# UIAPduino_Pro_Micro_CH32V006_V1dot0.net
KiCad netlist of a schematic drawn in EAGLE
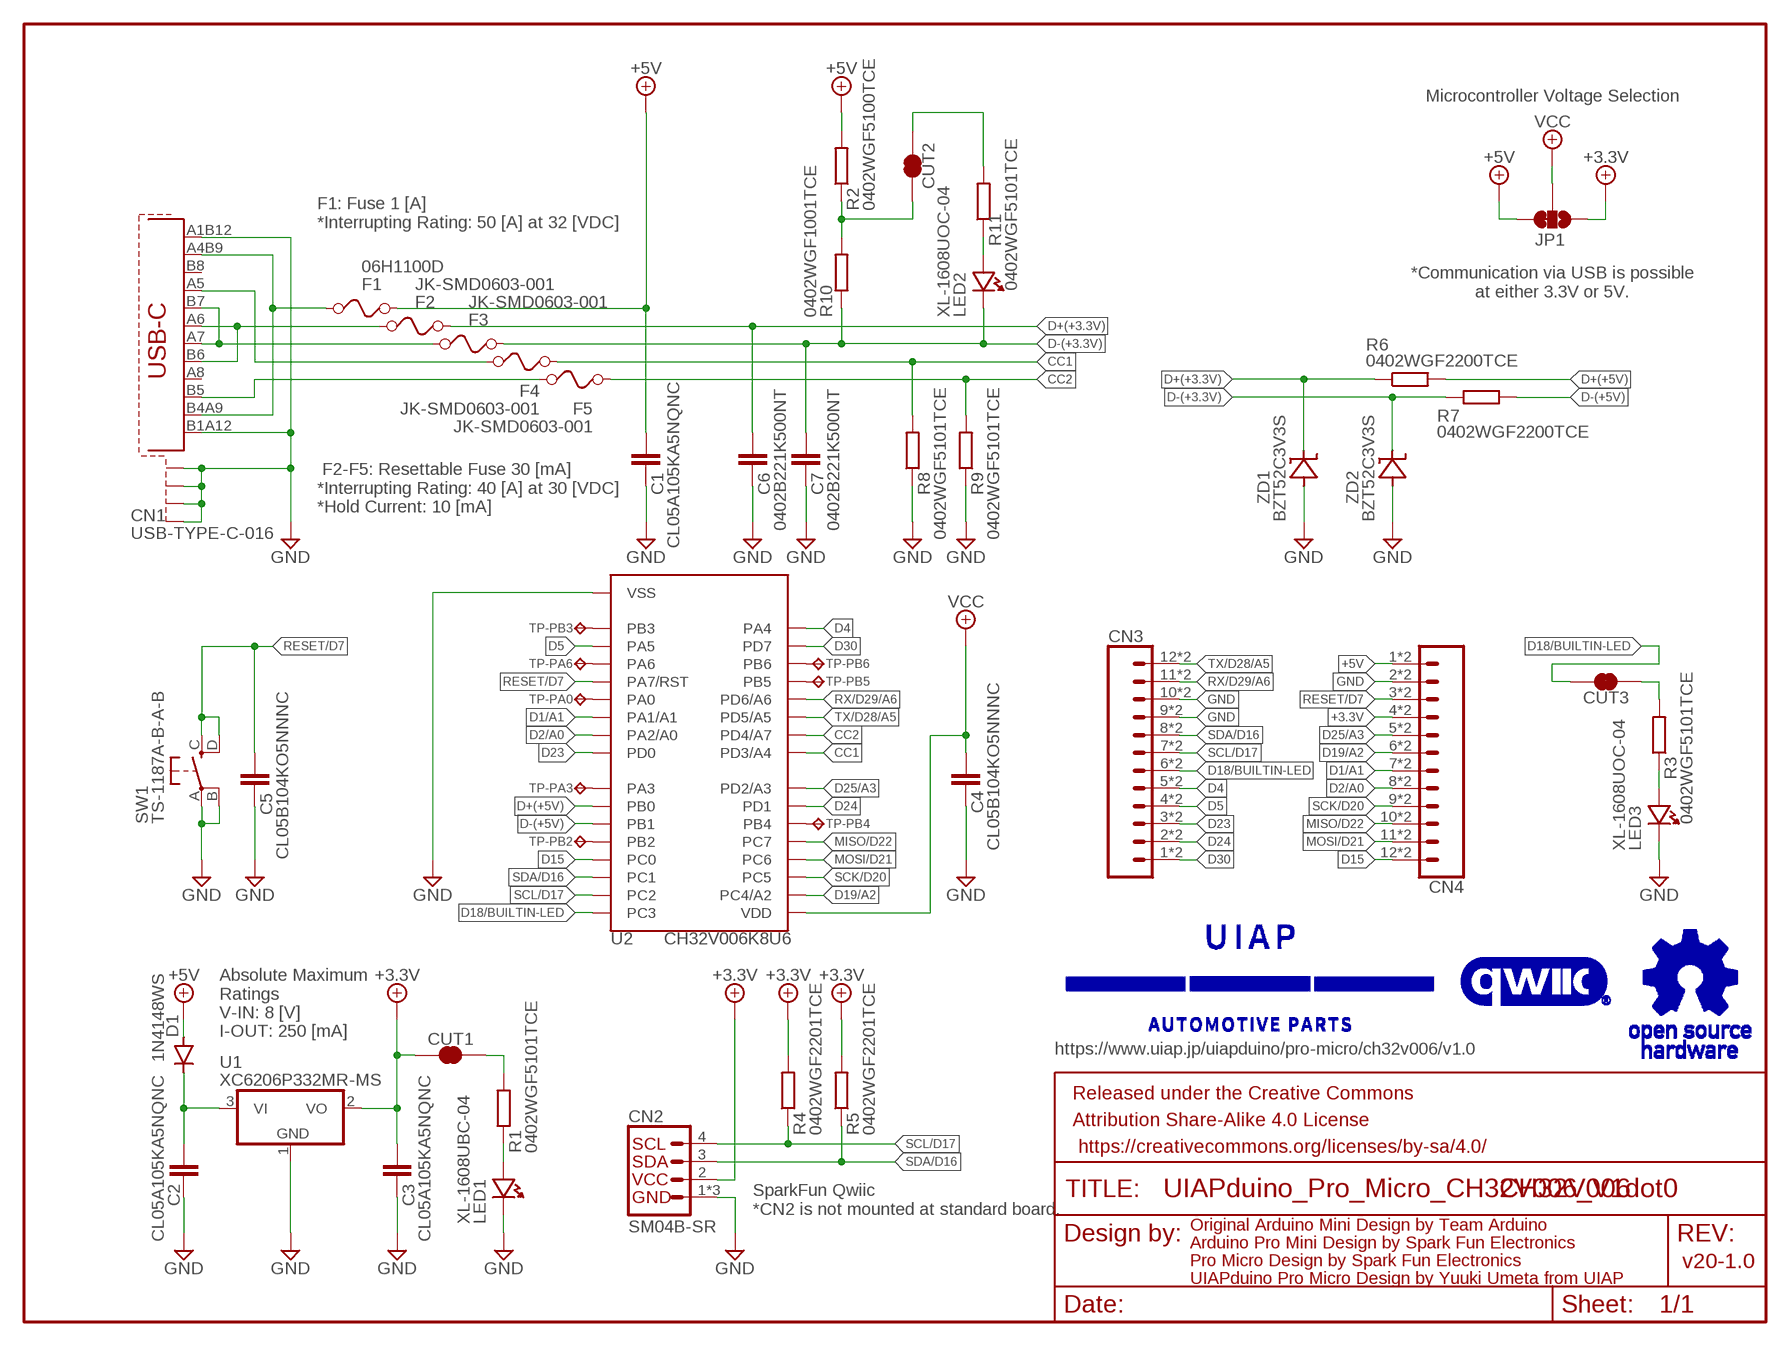
[diagram p0: schematic, sheet 1, part 1 of 2]
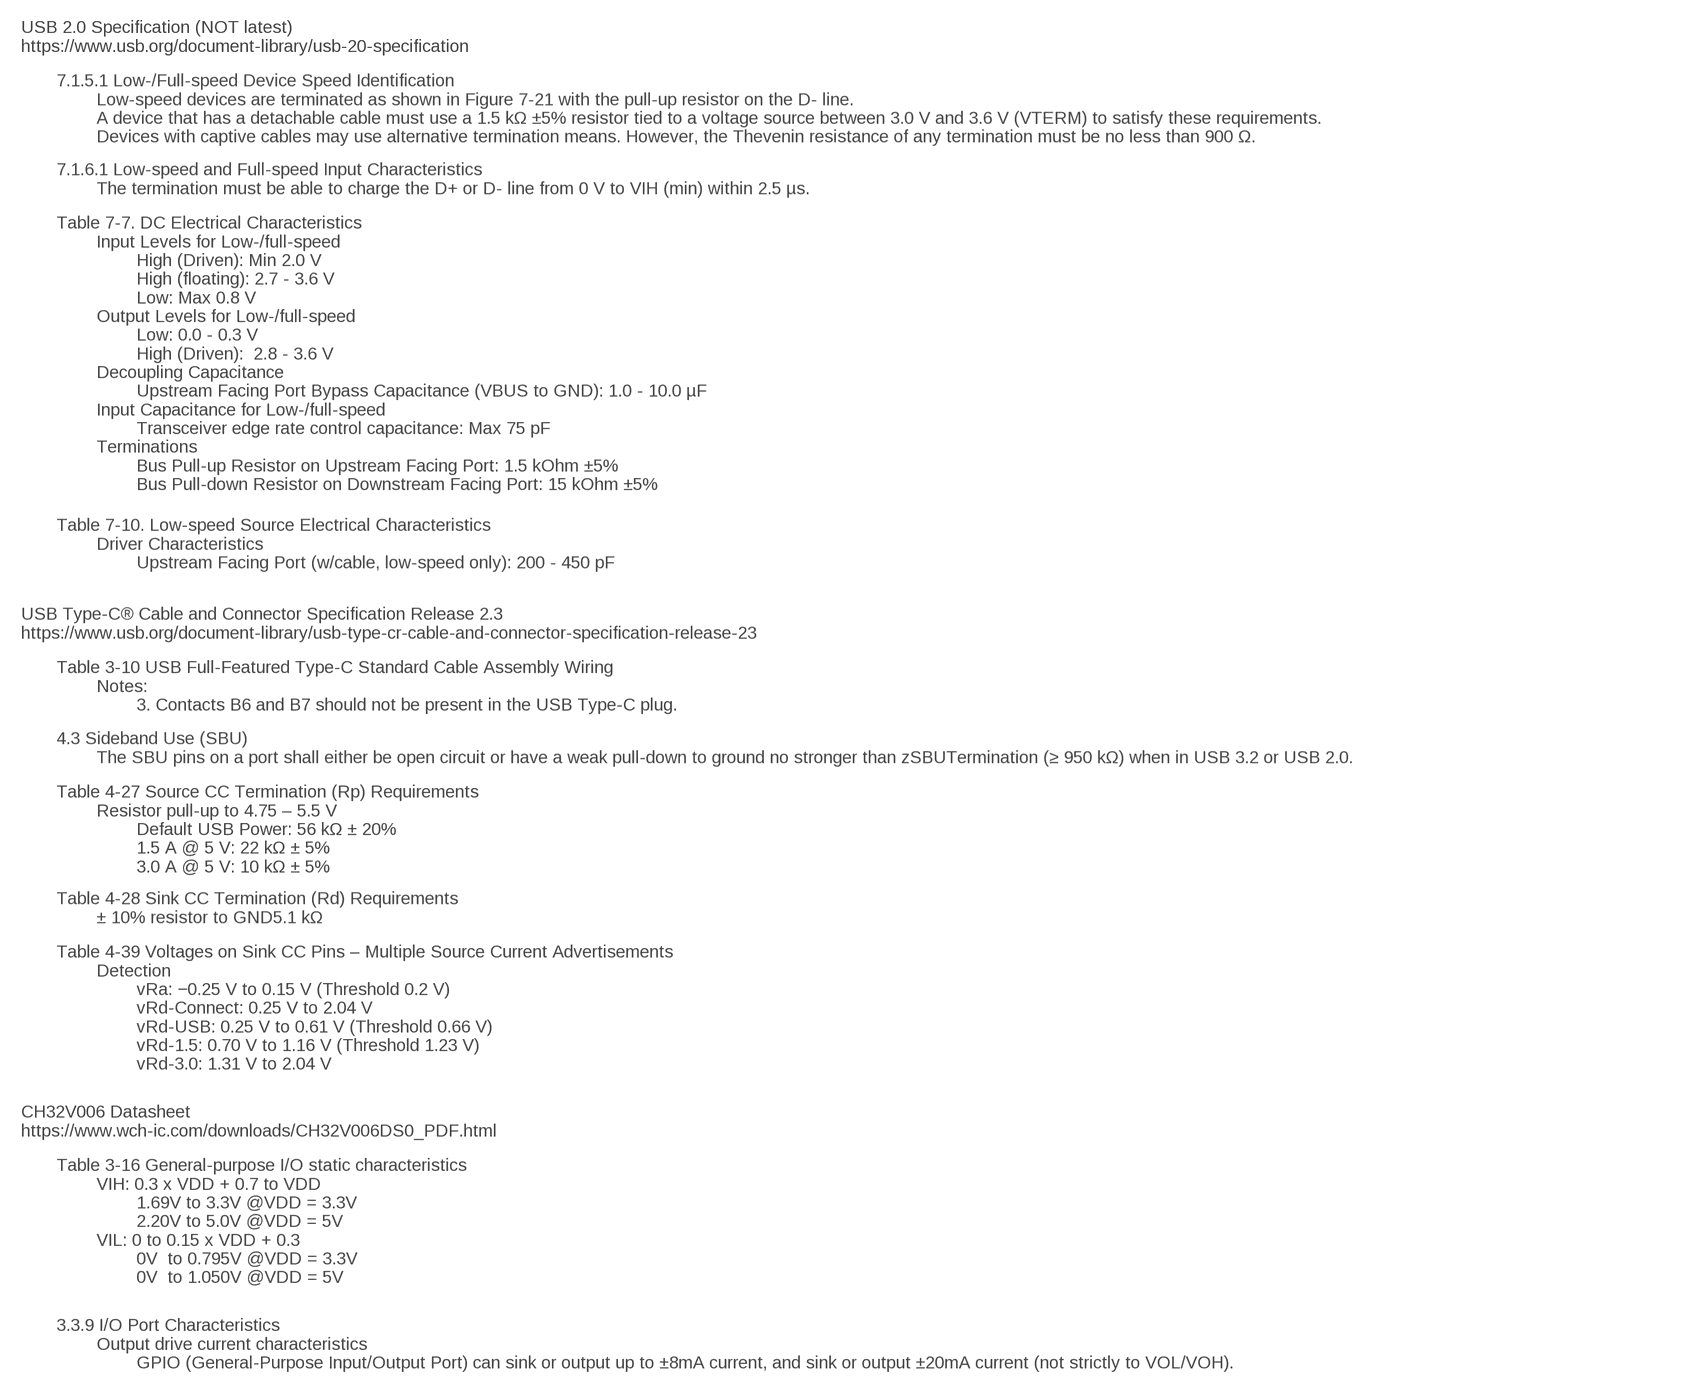
[diagram p1: schematic, sheet 1, part 2 of 2]

(export (version "E")
  (design (tool "Eeschema 10.0.6"))
  (components
    (comp (ref "C1")
      (value "CL05A105KA5NQNC")
      (footprint "eagle-import:1005")
      (libsource (lib "eagle-import") (part "C1005"))
    )
    (comp (ref "C2")
      (value "CL05A105KA5NQNC")
      (footprint "eagle-import:1005")
      (libsource (lib "eagle-import") (part "C1005"))
    )
    (comp (ref "C3")
      (value "CL05A105KA5NQNC")
      (footprint "eagle-import:1005")
      (libsource (lib "eagle-import") (part "C1005"))
    )
    (comp (ref "C4")
      (value "CL05B104KO5NNNC")
      (footprint "eagle-import:1005")
      (libsource (lib "eagle-import") (part "C1005"))
    )
    (comp (ref "C5")
      (value "CL05B104KO5NNNC")
      (footprint "eagle-import:1005")
      (libsource (lib "eagle-import") (part "C1005"))
    )
    (comp (ref "C6")
      (value "0402B221K500NT")
      (footprint "eagle-import:1005")
      (libsource (lib "eagle-import") (part "C1005"))
    )
    (comp (ref "C7")
      (value "0402B221K500NT")
      (footprint "eagle-import:1005")
      (libsource (lib "eagle-import") (part "C1005"))
    )
    (comp (ref "CN1")
      (value "USB-TYPE-C-016")
      (footprint "eagle-import:USB-TYPE-C-016")
      (libsource (lib "eagle-import") (part "USB-TYPE-C-016"))
    )
    (comp (ref "CN2")
      (value "SM04B-SR")
      (footprint "eagle-import:JST04_1MM_RA")
      (libsource (lib "eagle-import") (part "QWIIC_CONNECTORJS-1MM-GND"))
    )
    (comp (ref "CN3")
      (value "CONN_12CASTLE_0.9MM")
      (footprint "eagle-import:1X12_CASTELLATED_0.9MM")
      (libsource (lib "eagle-import") (part "CONN_12CASTLE_0.9MM"))
    )
    (comp (ref "CN4")
      (value "CONN_12CASTLE_0.9MM")
      (footprint "eagle-import:1X12_CASTELLATED_0.9MM")
      (libsource (lib "eagle-import") (part "CONN_12CASTLE_0.9MM"))
    )
    (comp (ref "CUT1")
      (value "SMT-JP-2-NC")
      (footprint "eagle-import:SMT-JUMPER_2_NC_SILK_ROUND")
      (libsource (lib "eagle-import") (part "SMT-JP-2-NC"))
    )
    (comp (ref "CUT2")
      (value "SMT-JP-2-NC")
      (footprint "eagle-import:SMT-JUMPER_2_NC_SILK_ROUND")
      (libsource (lib "eagle-import") (part "SMT-JP-2-NC"))
    )
    (comp (ref "CUT3")
      (value "SMT-JP-2-NC")
      (footprint "eagle-import:SMT-JUMPER_2_NC_SILK_ROUND")
      (libsource (lib "eagle-import") (part "SMT-JP-2-NC"))
    )
    (comp (ref "D1")
      (value "1N4148WS")
      (footprint "eagle-import:SOD323-R")
      (libsource (lib "eagle-import") (part "DIODE-SOD323-R"))
    )
    (comp (ref "F1")
      (value "06H1100D")
      (footprint "eagle-import:1608")
      (libsource (lib "eagle-import") (part "06H1100D"))
    )
    (comp (ref "F2")
      (value "JK-SMD0603-001")
      (footprint "eagle-import:1608")
      (libsource (lib "eagle-import") (part "06H1100D"))
    )
    (comp (ref "F3")
      (value "JK-SMD0603-001")
      (footprint "eagle-import:1608")
      (libsource (lib "eagle-import") (part "06H1100D"))
    )
    (comp (ref "F4")
      (value "JK-SMD0603-001")
      (footprint "eagle-import:1608")
      (libsource (lib "eagle-import") (part "06H1100D"))
    )
    (comp (ref "F5")
      (value "JK-SMD0603-001")
      (footprint "eagle-import:1608")
      (libsource (lib "eagle-import") (part "06H1100D"))
    )
    (comp (ref "FRAME1")
      (value "FRAME-LETTER")
      (footprint "eagle-import:CREATIVE_COMMONS")
      (libsource (lib "eagle-import") (part "FRAME-LETTER"))
    )
    (comp (ref "JP1")
      (value "SMT-JP-3-NO-NC")
      (footprint "eagle-import:SMT-JUMPER_3_1-NC_TRACE_SILK")
      (libsource (lib "eagle-import") (part "SMT-JP-3-NO-NC"))
    )
    (comp (ref "LED1")
      (value "XL-1608UBC-04")
      (footprint "eagle-import:1608-LED")
      (libsource (lib "eagle-import") (part "XL-1608UBC-04"))
    )
    (comp (ref "LED2")
      (value "XL-1608UOC-04")
      (footprint "eagle-import:1608-LED")
      (libsource (lib "eagle-import") (part "XL-1608UOC-04"))
    )
    (comp (ref "LED3")
      (value "XL-1608UOC-04")
      (footprint "eagle-import:1608-LED")
      (libsource (lib "eagle-import") (part "XL-1608UOC-04"))
    )
    (comp (ref "R1")
      (value "0402WGF5101TCE")
      (footprint "eagle-import:1005")
      (libsource (lib "eagle-import") (part "R1005"))
    )
    (comp (ref "R2")
      (value "0402WGF5100TCE")
      (footprint "eagle-import:1005")
      (libsource (lib "eagle-import") (part "R1005"))
    )
    (comp (ref "R3")
      (value "0402WGF5101TCE")
      (footprint "eagle-import:1005")
      (libsource (lib "eagle-import") (part "R1005"))
    )
    (comp (ref "R4")
      (value "0402WGF2201TCE")
      (footprint "eagle-import:1005")
      (libsource (lib "eagle-import") (part "R1005"))
    )
    (comp (ref "R5")
      (value "0402WGF2201TCE")
      (footprint "eagle-import:1005")
      (libsource (lib "eagle-import") (part "R1005"))
    )
    (comp (ref "R6")
      (value "0402WGF2200TCE")
      (footprint "eagle-import:1005")
      (libsource (lib "eagle-import") (part "R1005"))
    )
    (comp (ref "R7")
      (value "0402WGF2200TCE")
      (footprint "eagle-import:1005")
      (libsource (lib "eagle-import") (part "R1005"))
    )
    (comp (ref "R8")
      (value "0402WGF5101TCE")
      (footprint "eagle-import:1005")
      (libsource (lib "eagle-import") (part "R1005"))
    )
    (comp (ref "R9")
      (value "0402WGF5101TCE")
      (footprint "eagle-import:1005")
      (libsource (lib "eagle-import") (part "R1005"))
    )
    (comp (ref "R10")
      (value "0402WGF1001TCE")
      (footprint "eagle-import:1005")
      (libsource (lib "eagle-import") (part "R1005"))
    )
    (comp (ref "R11")
      (value "0402WGF5101TCE")
      (footprint "eagle-import:1005")
      (libsource (lib "eagle-import") (part "R1005"))
    )
    (comp (ref "SW1")
      (value "TS-1187A-B-A-B")
      (footprint "eagle-import:TS-1187A-B-A-B")
      (libsource (lib "eagle-import") (part "TS-1187A-B-A-B"))
    )
    (comp (ref "TP-PA0")
      (value "TPTP06R")
      (footprint "eagle-import:TP06R")
      (libsource (lib "eagle-import") (part "TPTP06R"))
    )
    (comp (ref "TP-PA3")
      (value "TPTP06R")
      (footprint "eagle-import:TP06R")
      (libsource (lib "eagle-import") (part "TPTP06R"))
    )
    (comp (ref "TP-PA6")
      (value "TPTP06R")
      (footprint "eagle-import:TP06R")
      (libsource (lib "eagle-import") (part "TPTP06R"))
    )
    (comp (ref "TP-PB2")
      (value "TPTP06R")
      (footprint "eagle-import:TP06R")
      (libsource (lib "eagle-import") (part "TPTP06R"))
    )
    (comp (ref "TP-PB3")
      (value "TPTP06R")
      (footprint "eagle-import:TP06R")
      (libsource (lib "eagle-import") (part "TPTP06R"))
    )
    (comp (ref "TP-PB4")
      (value "TPTP06R")
      (footprint "eagle-import:TP06R")
      (libsource (lib "eagle-import") (part "TPTP06R"))
    )
    (comp (ref "TP-PB5")
      (value "TPTP06R")
      (footprint "eagle-import:TP06R")
      (libsource (lib "eagle-import") (part "TPTP06R"))
    )
    (comp (ref "TP-PB6")
      (value "TPTP06R")
      (footprint "eagle-import:TP06R")
      (libsource (lib "eagle-import") (part "TPTP06R"))
    )
    (comp (ref "U1")
      (value "XC6206P332MR-MS")
      (footprint "eagle-import:SOT-23F_TOS")
      (libsource (lib "eagle-import") (part "XC6206P332MR-MS"))
    )
    (comp (ref "U2")
      (value "CH32V006K8U6")
      (footprint "eagle-import:QFN40P400X400X100-33T270")
      (libsource (lib "eagle-import") (part "CH32V006K8U6"))
    )
    (comp (ref "ZD1")
      (value "BZT52C3V3S")
      (footprint "eagle-import:SOD323-R")
      (libsource (lib "eagle-import") (part "BZT52C3V3S"))
    )
    (comp (ref "ZD2")
      (value "BZT52C3V3S")
      (footprint "eagle-import:SOD323-R")
      (libsource (lib "eagle-import") (part "BZT52C3V3S"))
    )
  )
  (nets
    (net (code "1") (name "+3.3V") (class "Default")
      (node (ref "C3") (pin "1") (pinfunction "1_1") (pintype "passive"))
      (node (ref "CN2") (pin "2") (pinfunction "2_2") (pintype "power_in"))
      (node (ref "CN4") (pin "4") (pinfunction "4_4") (pintype "passive"))
      (node (ref "CN4") (pin "4B") (pinfunction "4_4B") (pintype "passive"))
      (node (ref "CUT1") (pin "2") (pinfunction "2_2") (pintype "passive"))
      (node (ref "JP1") (pin "1") (pinfunction "1_1") (pintype "passive"))
      (node (ref "R4") (pin "2") (pinfunction "2_2") (pintype "passive"))
      (node (ref "R5") (pin "2") (pinfunction "2_2") (pintype "passive"))
      (node (ref "U1") (pin "2") (pinfunction "VO_2") (pintype "passive"))
    )
    (net (code "2") (name "+5V") (class "Default")
      (node (ref "C1") (pin "1") (pinfunction "1_1") (pintype "passive"))
      (node (ref "CN4") (pin "1") (pinfunction "1_1") (pintype "passive"))
      (node (ref "CN4") (pin "1B") (pinfunction "1_1B") (pintype "passive"))
      (node (ref "D1") (pin "A") (pinfunction "A_A") (pintype "passive"))
      (node (ref "F1") (pin "2") (pinfunction "2_2") (pintype "passive"))
      (node (ref "JP1") (pin "3") (pinfunction "3_3") (pintype "passive"))
      (node (ref "R2") (pin "2") (pinfunction "2_2") (pintype "passive"))
    )
    (net (code "3") (name "CC1") (class "Default")
      (node (ref "F4") (pin "2") (pinfunction "2_2") (pintype "passive"))
      (node (ref "R8") (pin "2") (pinfunction "2_2") (pintype "passive"))
      (node (ref "U2") (pin "25") (pinfunction "PD3/A4_25") (pintype "bidirectional"))
    )
    (net (code "4") (name "CC2") (class "Default")
      (node (ref "F5") (pin "2") (pinfunction "2_2") (pintype "passive"))
      (node (ref "R9") (pin "2") (pinfunction "2_2") (pintype "passive"))
      (node (ref "U2") (pin "26") (pinfunction "PD4/A7_26") (pintype "bidirectional"))
    )
    (net (code "5") (name "D+(+3.3V)") (class "Default")
      (node (ref "C6") (pin "1") (pinfunction "1_1") (pintype "passive"))
      (node (ref "F2") (pin "2") (pinfunction "2_2") (pintype "passive"))
      (node (ref "R6") (pin "1") (pinfunction "1_1") (pintype "passive"))
      (node (ref "ZD1") (pin "C") (pinfunction "C_C") (pintype "passive"))
    )
    (net (code "6") (name "D+(+5V)") (class "Default")
      (node (ref "R6") (pin "2") (pinfunction "2_2") (pintype "passive"))
      (node (ref "U2") (pin "10") (pinfunction "PB0_10") (pintype "bidirectional"))
    )
    (net (code "7") (name "D-(+3.3V)") (class "Default")
      (node (ref "C7") (pin "1") (pinfunction "1_1") (pintype "passive"))
      (node (ref "F3") (pin "2") (pinfunction "2_2") (pintype "passive"))
      (node (ref "LED2") (pin "2") (pinfunction "C_2") (pintype "passive"))
      (node (ref "R10") (pin "1") (pinfunction "1_1") (pintype "passive"))
      (node (ref "R7") (pin "1") (pinfunction "1_1") (pintype "passive"))
      (node (ref "ZD2") (pin "C") (pinfunction "C_C") (pintype "passive"))
    )
    (net (code "8") (name "D-(+5V)") (class "Default")
      (node (ref "R7") (pin "2") (pinfunction "2_2") (pintype "passive"))
      (node (ref "U2") (pin "11") (pinfunction "PB1_11") (pintype "bidirectional"))
    )
    (net (code "9") (name "D1{slash}A1") (class "Default")
      (node (ref "CN4") (pin "7") (pinfunction "7_7") (pintype "passive"))
      (node (ref "CN4") (pin "7B") (pinfunction "7_7B") (pintype "passive"))
      (node (ref "U2") (pin "6") (pinfunction "PA1/A1_6") (pintype "bidirectional"))
    )
    (net (code "10") (name "D2{slash}A0") (class "Default")
      (node (ref "CN4") (pin "8") (pinfunction "8_8") (pintype "passive"))
      (node (ref "CN4") (pin "8B") (pinfunction "8_8B") (pintype "passive"))
      (node (ref "U2") (pin "7") (pinfunction "PA2/A0_7") (pintype "bidirectional"))
    )
    (net (code "11") (name "D4") (class "Default")
      (node (ref "CN3") (pin "5") (pinfunction "5_5") (pintype "passive"))
      (node (ref "CN3") (pin "5B") (pinfunction "5_5B") (pintype "passive"))
      (node (ref "U2") (pin "32") (pinfunction "PA4_32") (pintype "bidirectional"))
    )
    (net (code "12") (name "D5") (class "Default")
      (node (ref "CN3") (pin "4") (pinfunction "4_4") (pintype "passive"))
      (node (ref "CN3") (pin "4B") (pinfunction "4_4B") (pintype "passive"))
      (node (ref "U2") (pin "2") (pinfunction "PA5_2") (pintype "bidirectional"))
    )
    (net (code "13") (name "D15") (class "Default")
      (node (ref "CN4") (pin "12") (pinfunction "12_12") (pintype "passive"))
      (node (ref "CN4") (pin "12B") (pinfunction "12_12B") (pintype "passive"))
      (node (ref "U2") (pin "13") (pinfunction "PC0_13") (pintype "bidirectional"))
    )
    (net (code "14") (name "D18{slash}BUILTIN-LED") (class "Default")
      (node (ref "CN3") (pin "6") (pinfunction "6_6") (pintype "passive"))
      (node (ref "CN3") (pin "6B") (pinfunction "6_6B") (pintype "passive"))
      (node (ref "CUT3") (pin "1") (pinfunction "1_1") (pintype "passive"))
      (node (ref "U2") (pin "16") (pinfunction "PC3_16") (pintype "bidirectional"))
    )
    (net (code "15") (name "D19{slash}A2") (class "Default")
      (node (ref "CN4") (pin "6") (pinfunction "6_6") (pintype "passive"))
      (node (ref "CN4") (pin "6B") (pinfunction "6_6B") (pintype "passive"))
      (node (ref "U2") (pin "18") (pinfunction "PC4/A2_18") (pintype "bidirectional"))
    )
    (net (code "16") (name "D23") (class "Default")
      (node (ref "CN3") (pin "3") (pinfunction "3_3") (pintype "passive"))
      (node (ref "CN3") (pin "3B") (pinfunction "3_3B") (pintype "passive"))
      (node (ref "U2") (pin "8") (pinfunction "PD0_8") (pintype "bidirectional"))
    )
    (net (code "17") (name "D24") (class "Default")
      (node (ref "CN3") (pin "2") (pinfunction "2_2") (pintype "passive"))
      (node (ref "CN3") (pin "2B") (pinfunction "2_2B") (pintype "passive"))
      (node (ref "U2") (pin "23") (pinfunction "PD1_23") (pintype "bidirectional"))
    )
    (net (code "18") (name "D25{slash}A3") (class "Default")
      (node (ref "CN4") (pin "5") (pinfunction "5_5") (pintype "passive"))
      (node (ref "CN4") (pin "5B") (pinfunction "5_5B") (pintype "passive"))
      (node (ref "U2") (pin "24") (pinfunction "PD2/A3_24") (pintype "bidirectional"))
    )
    (net (code "19") (name "D30") (class "Default")
      (node (ref "CN3") (pin "1") (pinfunction "1_1") (pintype "passive"))
      (node (ref "CN3") (pin "1B") (pinfunction "1_1B") (pintype "passive"))
      (node (ref "U2") (pin "31") (pinfunction "PD7_31") (pintype "bidirectional"))
    )
    (net (code "20") (name "GND") (class "Default")
      (node (ref "C1") (pin "2") (pinfunction "2_2") (pintype "passive"))
      (node (ref "C2") (pin "2") (pinfunction "2_2") (pintype "passive"))
      (node (ref "C3") (pin "2") (pinfunction "2_2") (pintype "passive"))
      (node (ref "C4") (pin "2") (pinfunction "2_2") (pintype "passive"))
      (node (ref "C5") (pin "2") (pinfunction "2_2") (pintype "passive"))
      (node (ref "C6") (pin "2") (pinfunction "2_2") (pintype "passive"))
      (node (ref "C7") (pin "2") (pinfunction "2_2") (pintype "passive"))
      (node (ref "CN1") (pin "A1B12") (pinfunction "GND_A1B12") (pintype "power_in"))
      (node (ref "CN1") (pin "B1A12") (pinfunction "GND_B1A12") (pintype "power_in"))
      (node (ref "CN1") (pin "S1") (pinfunction "S1_S1") (pintype "passive"))
      (node (ref "CN1") (pin "S1B") (pinfunction "S1_S1B") (pintype "passive"))
      (node (ref "CN1") (pin "S2") (pinfunction "S2_S2") (pintype "passive"))
      (node (ref "CN1") (pin "S2B") (pinfunction "S2_S2B") (pintype "passive"))
      (node (ref "CN1") (pin "S3") (pinfunction "S3_S3") (pintype "passive"))
      (node (ref "CN1") (pin "S3B") (pinfunction "S3_S3B") (pintype "passive"))
      (node (ref "CN1") (pin "S4") (pinfunction "S4_S4") (pintype "passive"))
      (node (ref "CN1") (pin "S4B") (pinfunction "S4_S4B") (pintype "passive"))
      (node (ref "CN2") (pin "1") (pinfunction "1_1") (pintype "power_in"))
      (node (ref "CN2") (pin "NC1") (pinfunction "1_NC1") (pintype "power_in"))
      (node (ref "CN2") (pin "NC2") (pinfunction "1_NC2") (pintype "power_in"))
      (node (ref "CN3") (pin "10") (pinfunction "10_10") (pintype "passive"))
      (node (ref "CN3") (pin "10B") (pinfunction "10_10B") (pintype "passive"))
      (node (ref "CN3") (pin "9") (pinfunction "9_9") (pintype "passive"))
      (node (ref "CN3") (pin "9B") (pinfunction "9_9B") (pintype "passive"))
      (node (ref "CN4") (pin "2") (pinfunction "2_2") (pintype "passive"))
      (node (ref "CN4") (pin "2B") (pinfunction "2_2B") (pintype "passive"))
      (node (ref "LED1") (pin "2") (pinfunction "C_2") (pintype "passive"))
      (node (ref "LED3") (pin "2") (pinfunction "C_2") (pintype "passive"))
      (node (ref "R8") (pin "1") (pinfunction "1_1") (pintype "passive"))
      (node (ref "R9") (pin "1") (pinfunction "1_1") (pintype "passive"))
      (node (ref "SW1") (pin "A") (pinfunction "P_A") (pintype "passive"))
      (node (ref "SW1") (pin "B") (pinfunction "P1_B") (pintype "passive"))
      (node (ref "U1") (pin "1") (pinfunction "GND_1") (pintype "passive"))
      (node (ref "U2") (pin "0") (pinfunction "VSS_0") (pintype "power_in"))
      (node (ref "U2") (pin "P-VIA$1") (pinfunction "VSS_P-VIA$1") (pintype "power_in"))
      (node (ref "U2") (pin "P-VIA$2") (pinfunction "VSS_P-VIA$2") (pintype "power_in"))
      (node (ref "U2") (pin "P-VIA$3") (pinfunction "VSS_P-VIA$3") (pintype "power_in"))
      (node (ref "U2") (pin "P-VIA$4") (pinfunction "VSS_P-VIA$4") (pintype "power_in"))
      (node (ref "U2") (pin "P-VIA$5") (pinfunction "VSS_P-VIA$5") (pintype "power_in"))
      (node (ref "U2") (pin "P-VIA$6") (pinfunction "VSS_P-VIA$6") (pintype "power_in"))
      (node (ref "U2") (pin "P-VIA$7") (pinfunction "VSS_P-VIA$7") (pintype "power_in"))
      (node (ref "U2") (pin "P-VIA$8") (pinfunction "VSS_P-VIA$8") (pintype "power_in"))
      (node (ref "U2") (pin "P-VIA$9") (pinfunction "VSS_P-VIA$9") (pintype "power_in"))
      (node (ref "ZD1") (pin "A") (pinfunction "A_A") (pintype "passive"))
      (node (ref "ZD2") (pin "A") (pinfunction "A_A") (pintype "passive"))
    )
    (net (code "21") (name "MISO{slash}D22") (class "Default")
      (node (ref "CN4") (pin "10") (pinfunction "10_10") (pintype "passive"))
      (node (ref "CN4") (pin "10B") (pinfunction "10_10B") (pintype "passive"))
      (node (ref "U2") (pin "21") (pinfunction "PC7_21") (pintype "bidirectional"))
    )
    (net (code "22") (name "MOSI{slash}D21") (class "Default")
      (node (ref "CN4") (pin "11") (pinfunction "11_11") (pintype "passive"))
      (node (ref "CN4") (pin "11B") (pinfunction "11_11B") (pintype "passive"))
      (node (ref "U2") (pin "20") (pinfunction "PC6_20") (pintype "bidirectional"))
    )
    (net (code "23") (name "Net-(CN1-CC1)") (class "Default")
      (node (ref "CN1") (pin "A5") (pinfunction "CC1_A5") (pintype "passive"))
      (node (ref "F4") (pin "1") (pinfunction "1_1") (pintype "passive"))
    )
    (net (code "24") (name "Net-(CN1-CC2)") (class "Default")
      (node (ref "CN1") (pin "B5") (pinfunction "CC2_B5") (pintype "passive"))
      (node (ref "F5") (pin "1") (pinfunction "1_1") (pintype "passive"))
    )
    (net (code "25") (name "Net-(CN1-DN1)") (class "Default")
      (node (ref "CN1") (pin "A7") (pinfunction "DN1_A7") (pintype "passive"))
      (node (ref "CN1") (pin "B7") (pinfunction "DN2_B7") (pintype "passive"))
      (node (ref "F3") (pin "1") (pinfunction "1_1") (pintype "passive"))
    )
    (net (code "26") (name "Net-(CN1-DP1)") (class "Default")
      (node (ref "CN1") (pin "A6") (pinfunction "DP1_A6") (pintype "passive"))
      (node (ref "CN1") (pin "B6") (pinfunction "DP2_B6") (pintype "passive"))
      (node (ref "F2") (pin "1") (pinfunction "1_1") (pintype "passive"))
    )
    (net (code "27") (name "Net-(CN1-VBUS-PadA4B9)") (class "Default")
      (node (ref "CN1") (pin "A4B9") (pinfunction "VBUS_A4B9") (pintype "power_in"))
      (node (ref "CN1") (pin "B4A9") (pinfunction "VBUS_B4A9") (pintype "power_in"))
      (node (ref "F1") (pin "1") (pinfunction "1_1") (pintype "passive"))
    )
    (net (code "28") (name "Net-(CUT1-Pad1)") (class "Default")
      (node (ref "CUT1") (pin "1") (pinfunction "1_1") (pintype "passive"))
      (node (ref "R1") (pin "2") (pinfunction "2_2") (pintype "passive"))
    )
    (net (code "29") (name "Net-(CUT2-Pad1)") (class "Default")
      (node (ref "CUT2") (pin "1") (pinfunction "1_1") (pintype "passive"))
      (node (ref "R11") (pin "2") (pinfunction "2_2") (pintype "passive"))
    )
    (net (code "30") (name "Net-(CUT2-Pad2)") (class "Default")
      (node (ref "CUT2") (pin "2") (pinfunction "2_2") (pintype "passive"))
      (node (ref "R10") (pin "2") (pinfunction "2_2") (pintype "passive"))
      (node (ref "R2") (pin "1") (pinfunction "1_1") (pintype "passive"))
    )
    (net (code "31") (name "Net-(CUT3-Pad2)") (class "Default")
      (node (ref "CUT3") (pin "2") (pinfunction "2_2") (pintype "passive"))
      (node (ref "R3") (pin "2") (pinfunction "2_2") (pintype "passive"))
    )
    (net (code "32") (name "Net-(LED1-A)") (class "Default")
      (node (ref "LED1") (pin "1") (pinfunction "A_1") (pintype "passive"))
      (node (ref "R1") (pin "1") (pinfunction "1_1") (pintype "passive"))
    )
    (net (code "33") (name "Net-(LED2-A)") (class "Default")
      (node (ref "LED2") (pin "1") (pinfunction "A_1") (pintype "passive"))
      (node (ref "R11") (pin "1") (pinfunction "1_1") (pintype "passive"))
    )
    (net (code "34") (name "Net-(LED3-A)") (class "Default")
      (node (ref "LED3") (pin "1") (pinfunction "A_1") (pintype "passive"))
      (node (ref "R3") (pin "1") (pinfunction "1_1") (pintype "passive"))
    )
    (net (code "35") (name "Net-(U1-VI)") (class "Default")
      (node (ref "C2") (pin "1") (pinfunction "1_1") (pintype "passive"))
      (node (ref "D1") (pin "C") (pinfunction "C_C") (pintype "passive"))
      (node (ref "U1") (pin "3") (pinfunction "VI_3") (pintype "input"))
    )
    (net (code "36") (name "Net-(U2-PA0)") (class "Default")
      (node (ref "TP-PA0") (pin "TP") (pinfunction "TP_TP") (pintype "input"))
      (node (ref "U2") (pin "5") (pinfunction "PA0_5") (pintype "bidirectional"))
    )
    (net (code "37") (name "Net-(U2-PA3)") (class "Default")
      (node (ref "TP-PA3") (pin "TP") (pinfunction "TP_TP") (pintype "input"))
      (node (ref "U2") (pin "9") (pinfunction "PA3_9") (pintype "bidirectional"))
    )
    (net (code "38") (name "Net-(U2-PA6)") (class "Default")
      (node (ref "TP-PA6") (pin "TP") (pinfunction "TP_TP") (pintype "input"))
      (node (ref "U2") (pin "3") (pinfunction "PA6_3") (pintype "bidirectional"))
    )
    (net (code "39") (name "Net-(U2-PB2)") (class "Default")
      (node (ref "TP-PB2") (pin "TP") (pinfunction "TP_TP") (pintype "input"))
      (node (ref "U2") (pin "12") (pinfunction "PB2_12") (pintype "bidirectional"))
    )
    (net (code "40") (name "Net-(U2-PB3)") (class "Default")
      (node (ref "TP-PB3") (pin "TP") (pinfunction "TP_TP") (pintype "input"))
      (node (ref "U2") (pin "1") (pinfunction "PB3_1") (pintype "bidirectional"))
    )
    (net (code "41") (name "Net-(U2-PB4)") (class "Default")
      (node (ref "TP-PB4") (pin "TP") (pinfunction "TP_TP") (pintype "input"))
      (node (ref "U2") (pin "22") (pinfunction "PB4_22") (pintype "bidirectional"))
    )
    (net (code "42") (name "Net-(U2-PB5)") (class "Default")
      (node (ref "TP-PB5") (pin "TP") (pinfunction "TP_TP") (pintype "input"))
      (node (ref "U2") (pin "29") (pinfunction "PB5_29") (pintype "bidirectional"))
    )
    (net (code "43") (name "Net-(U2-PB6)") (class "Default")
      (node (ref "TP-PB6") (pin "TP") (pinfunction "TP_TP") (pintype "input"))
      (node (ref "U2") (pin "30") (pinfunction "PB6_30") (pintype "bidirectional"))
    )
    (net (code "44") (name "RESET{slash}D7") (class "Default")
      (node (ref "C5") (pin "1") (pinfunction "1_1") (pintype "passive"))
      (node (ref "CN4") (pin "3") (pinfunction "3_3") (pintype "passive"))
      (node (ref "CN4") (pin "3B") (pinfunction "3_3B") (pintype "passive"))
      (node (ref "SW1") (pin "C") (pinfunction "S_C") (pintype "passive"))
      (node (ref "SW1") (pin "D") (pinfunction "S1_D") (pintype "passive"))
      (node (ref "U2") (pin "4") (pinfunction "PA7/RST_4") (pintype "bidirectional"))
    )
    (net (code "45") (name "RX{slash}D29{slash}A6") (class "Default")
      (node (ref "CN3") (pin "11") (pinfunction "11_11") (pintype "passive"))
      (node (ref "CN3") (pin "11B") (pinfunction "11_11B") (pintype "passive"))
      (node (ref "U2") (pin "28") (pinfunction "PD6/A6_28") (pintype "bidirectional"))
    )
    (net (code "46") (name "SCK{slash}D20") (class "Default")
      (node (ref "CN4") (pin "9") (pinfunction "9_9") (pintype "passive"))
      (node (ref "CN4") (pin "9B") (pinfunction "9_9B") (pintype "passive"))
      (node (ref "U2") (pin "19") (pinfunction "PC5_19") (pintype "bidirectional"))
    )
    (net (code "47") (name "SCL{slash}D17") (class "Default")
      (node (ref "CN2") (pin "4") (pinfunction "4_4") (pintype "passive"))
      (node (ref "CN3") (pin "7") (pinfunction "7_7") (pintype "passive"))
      (node (ref "CN3") (pin "7B") (pinfunction "7_7B") (pintype "passive"))
      (node (ref "R4") (pin "1") (pinfunction "1_1") (pintype "passive"))
      (node (ref "U2") (pin "15") (pinfunction "PC2_15") (pintype "bidirectional"))
    )
    (net (code "48") (name "SDA{slash}D16") (class "Default")
      (node (ref "CN2") (pin "3") (pinfunction "3_3") (pintype "passive"))
      (node (ref "CN3") (pin "8") (pinfunction "8_8") (pintype "passive"))
      (node (ref "CN3") (pin "8B") (pinfunction "8_8B") (pintype "passive"))
      (node (ref "R5") (pin "1") (pinfunction "1_1") (pintype "passive"))
      (node (ref "U2") (pin "14") (pinfunction "PC1_14") (pintype "bidirectional"))
    )
    (net (code "49") (name "TX{slash}D28{slash}A5") (class "Default")
      (node (ref "CN3") (pin "12") (pinfunction "12_12") (pintype "passive"))
      (node (ref "CN3") (pin "12B") (pinfunction "12_12B") (pintype "passive"))
      (node (ref "U2") (pin "27") (pinfunction "PD5/A5_27") (pintype "bidirectional"))
    )
    (net (code "50") (name "VCC") (class "Default")
      (node (ref "C4") (pin "1") (pinfunction "1_1") (pintype "passive"))
      (node (ref "JP1") (pin "2") (pinfunction "2_2") (pintype "passive"))
      (node (ref "U2") (pin "17") (pinfunction "VDD_17") (pintype "power_in"))
    )
    (net (code "51") (name "unconnected-(CN1-SBU1-PadA8)") (class "Default")
      (node (ref "CN1") (pin "A8") (pinfunction "SBU1_A8") (pintype "passive"))
    )
    (net (code "52") (name "unconnected-(CN1-SBU2-PadB8)") (class "Default")
      (node (ref "CN1") (pin "B8") (pinfunction "SBU2_B8") (pintype "passive"))
    )
  )
)
